# Raspberry_Pi.net
KiCad netlist of a schematic drawn in Altium Designer
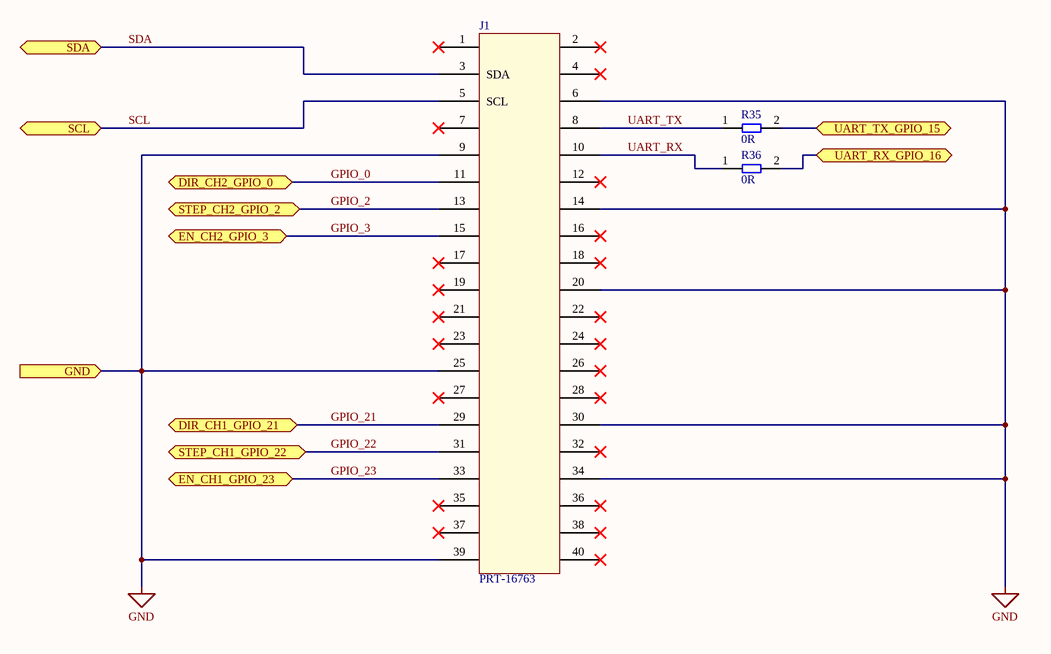
[diagram p0: Raspberry Pi.SchDoc]

(export (version "E")
  (design (tool "Eeschema 10.0.6"))
  (components
    (comp (ref "J1")
      (value "PRT-16763")
      (footprint "FP-SFH11-PBPC-D20-ST-BK-MFG")
      (description "Headers & Wire Housings Extended GPIO Female Header - 2x20 Pin (16mm/7.30mm)")
      (libsource (lib "Callisto Control Board") (part "Raspberry Pi 3+ Header"))
    )
    (comp (ref "R35")
      (value "0R")
      (footprint "0805 Resistor - IPC A")
      (description "Thick Film Resistors - SMD 0 Ohms 125 mW 0805 5%\r\nRC0805JR-070RL")
      (libsource (lib "Callisto Control Board") (part "RC0805JR-070RL"))
    )
    (comp (ref "R36")
      (value "0R")
      (footprint "0805 Resistor - IPC A")
      (description "Thick Film Resistors - SMD 0 Ohms 125 mW 0805 5%\r\nRC0805JR-070RL")
      (libsource (lib "Callisto Control Board") (part "RC0805JR-070RL"))
    )
  )
  (nets
    (net (code "1") (name "/GPIO_0") (class "Default")
      (node (ref "J1") (pin "11") (pinfunction "11_11") (pintype "passive"))
    )
    (net (code "2") (name "/GPIO_2") (class "Default")
      (node (ref "J1") (pin "13") (pinfunction "13_13") (pintype "passive"))
    )
    (net (code "3") (name "/GPIO_3") (class "Default")
      (node (ref "J1") (pin "15") (pinfunction "15_15") (pintype "passive"))
    )
    (net (code "4") (name "/GPIO_21") (class "Default")
      (node (ref "J1") (pin "29") (pinfunction "29_29") (pintype "passive"))
    )
    (net (code "5") (name "/GPIO_22") (class "Default")
      (node (ref "J1") (pin "31") (pinfunction "31_31") (pintype "passive"))
    )
    (net (code "6") (name "/GPIO_23") (class "Default")
      (node (ref "J1") (pin "33") (pinfunction "33_33") (pintype "passive"))
    )
    (net (code "7") (name "/SCL") (class "Default")
      (node (ref "J1") (pin "5") (pinfunction "SCL_5") (pintype "passive"))
    )
    (net (code "8") (name "/SDA") (class "Default")
      (node (ref "J1") (pin "3") (pinfunction "SDA_3") (pintype "passive"))
    )
    (net (code "9") (name "/UART_RX") (class "Default")
      (node (ref "J1") (pin "10") (pinfunction "10_10") (pintype "passive"))
      (node (ref "R36") (pin "1") (pintype "passive"))
    )
    (net (code "10") (name "/UART_RX_GPIO_16") (class "Default")
      (node (ref "R36") (pin "2") (pintype "passive"))
    )
    (net (code "11") (name "/UART_TX") (class "Default")
      (node (ref "J1") (pin "8") (pinfunction "8_8") (pintype "passive"))
      (node (ref "R35") (pin "1") (pintype "passive"))
    )
    (net (code "12") (name "/UART_TX_GPIO_15") (class "Default")
      (node (ref "R35") (pin "2") (pintype "passive"))
    )
    (net (code "13") (name "GND") (class "Default")
      (node (ref "J1") (pin "14") (pinfunction "14_14") (pintype "passive"))
      (node (ref "J1") (pin "20") (pinfunction "20_20") (pintype "passive"))
      (node (ref "J1") (pin "25") (pinfunction "25_25") (pintype "passive"))
      (node (ref "J1") (pin "30") (pinfunction "30_30") (pintype "passive"))
      (node (ref "J1") (pin "34") (pinfunction "34_34") (pintype "passive"))
      (node (ref "J1") (pin "39") (pinfunction "39_39") (pintype "passive"))
      (node (ref "J1") (pin "6") (pinfunction "6_6") (pintype "passive"))
      (node (ref "J1") (pin "9") (pinfunction "9_9") (pintype "passive"))
    )
    (net (code "14") (name "unconnected-(J1-Pad1)") (class "Default")
      (node (ref "J1") (pin "1") (pintype "passive+no_connect"))
    )
    (net (code "15") (name "unconnected-(J1-Pad2)") (class "Default")
      (node (ref "J1") (pin "2") (pintype "passive+no_connect"))
    )
    (net (code "16") (name "unconnected-(J1-Pad4)") (class "Default")
      (node (ref "J1") (pin "4") (pintype "passive+no_connect"))
    )
    (net (code "17") (name "unconnected-(J1-Pad7)") (class "Default")
      (node (ref "J1") (pin "7") (pinfunction "7_7") (pintype "passive+no_connect"))
    )
    (net (code "18") (name "unconnected-(J1-Pad12)") (class "Default")
      (node (ref "J1") (pin "12") (pinfunction "12_12") (pintype "passive+no_connect"))
    )
    (net (code "19") (name "unconnected-(J1-Pad16)") (class "Default")
      (node (ref "J1") (pin "16") (pinfunction "16_16") (pintype "passive+no_connect"))
    )
    (net (code "20") (name "unconnected-(J1-Pad17)") (class "Default")
      (node (ref "J1") (pin "17") (pinfunction "17_17") (pintype "passive+no_connect"))
    )
    (net (code "21") (name "unconnected-(J1-Pad18)") (class "Default")
      (node (ref "J1") (pin "18") (pinfunction "18_18") (pintype "passive+no_connect"))
    )
    (net (code "22") (name "unconnected-(J1-Pad19)") (class "Default")
      (node (ref "J1") (pin "19") (pinfunction "19_19") (pintype "passive+no_connect"))
    )
    (net (code "23") (name "unconnected-(J1-Pad21)") (class "Default")
      (node (ref "J1") (pin "21") (pinfunction "21_21") (pintype "passive+no_connect"))
    )
    (net (code "24") (name "unconnected-(J1-Pad22)") (class "Default")
      (node (ref "J1") (pin "22") (pinfunction "22_22") (pintype "passive+no_connect"))
    )
    (net (code "25") (name "unconnected-(J1-Pad23)") (class "Default")
      (node (ref "J1") (pin "23") (pinfunction "23_23") (pintype "passive+no_connect"))
    )
    (net (code "26") (name "unconnected-(J1-Pad24)") (class "Default")
      (node (ref "J1") (pin "24") (pinfunction "24_24") (pintype "passive+no_connect"))
    )
    (net (code "27") (name "unconnected-(J1-Pad26)") (class "Default")
      (node (ref "J1") (pin "26") (pinfunction "26_26") (pintype "passive+no_connect"))
    )
    (net (code "28") (name "unconnected-(J1-Pad27)") (class "Default")
      (node (ref "J1") (pin "27") (pinfunction "27_27") (pintype "passive+no_connect"))
    )
    (net (code "29") (name "unconnected-(J1-Pad28)") (class "Default")
      (node (ref "J1") (pin "28") (pinfunction "28_28") (pintype "passive+no_connect"))
    )
    (net (code "30") (name "unconnected-(J1-Pad32)") (class "Default")
      (node (ref "J1") (pin "32") (pinfunction "32_32") (pintype "passive+no_connect"))
    )
    (net (code "31") (name "unconnected-(J1-Pad35)") (class "Default")
      (node (ref "J1") (pin "35") (pinfunction "35_35") (pintype "passive+no_connect"))
    )
    (net (code "32") (name "unconnected-(J1-Pad36)") (class "Default")
      (node (ref "J1") (pin "36") (pinfunction "36_36") (pintype "passive+no_connect"))
    )
    (net (code "33") (name "unconnected-(J1-Pad37)") (class "Default")
      (node (ref "J1") (pin "37") (pinfunction "37_37") (pintype "passive+no_connect"))
    )
    (net (code "34") (name "unconnected-(J1-Pad38)") (class "Default")
      (node (ref "J1") (pin "38") (pinfunction "38_38") (pintype "passive+no_connect"))
    )
    (net (code "35") (name "unconnected-(J1-Pad40)") (class "Default")
      (node (ref "J1") (pin "40") (pinfunction "40_40") (pintype "passive+no_connect"))
    )
  )
)
